# mcu.net
KiCad netlist of a schematic drawn in Altium Designer
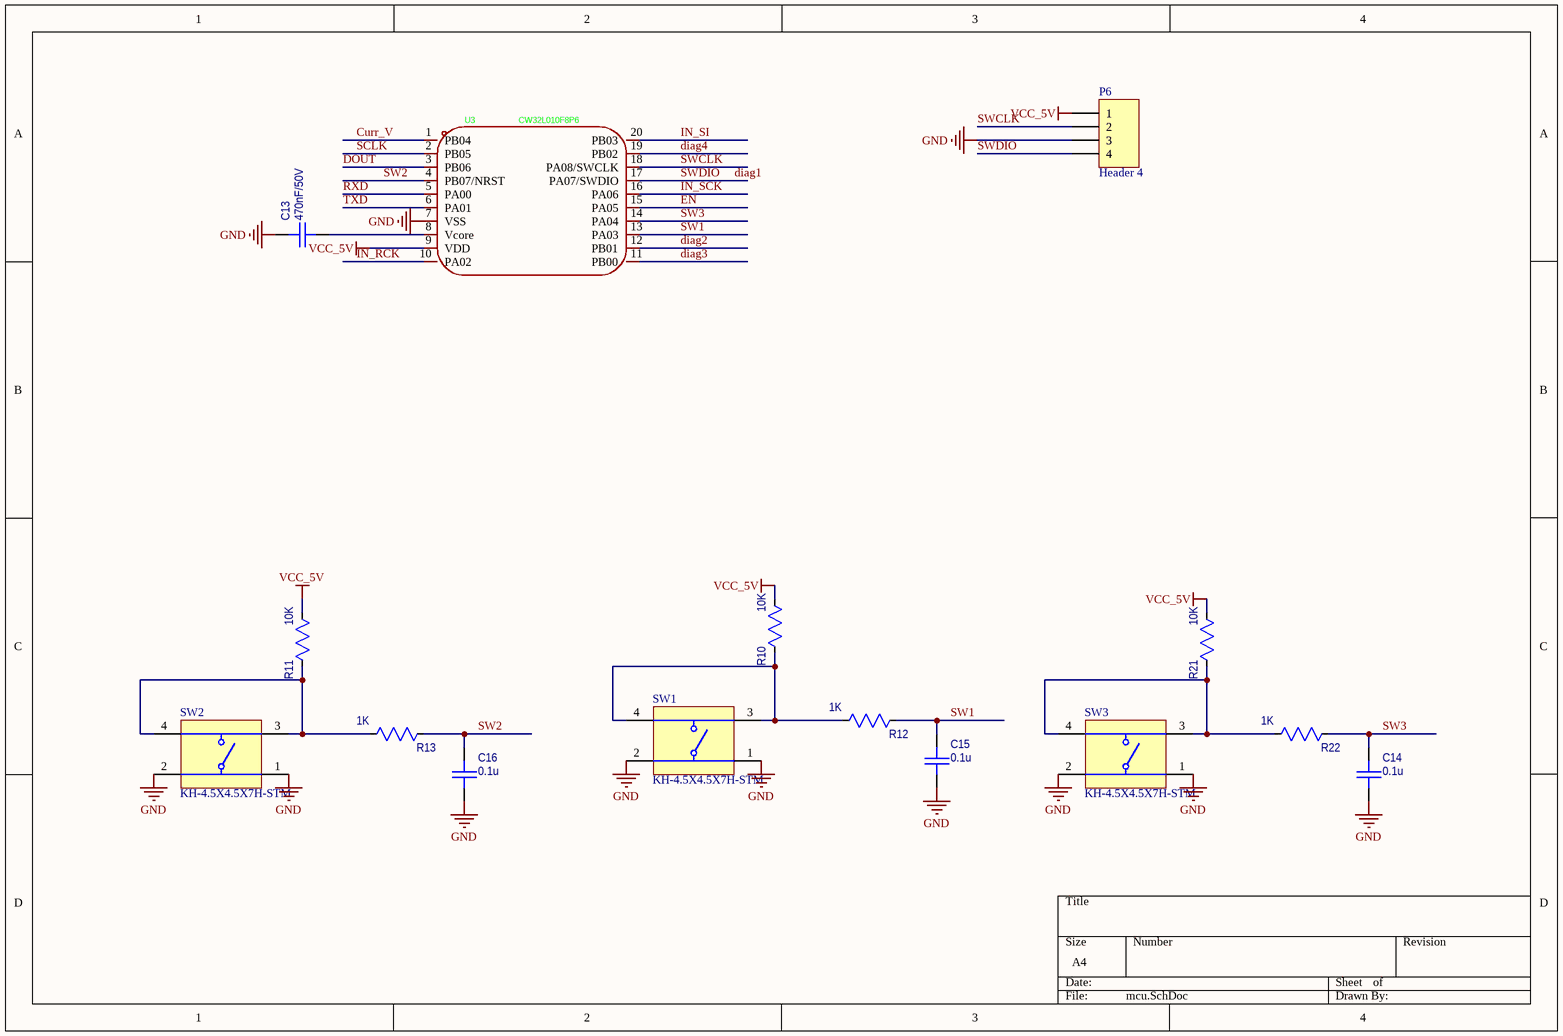
[diagram p0: mcu.SchDoc]

(export (version "E")
  (design (tool "Eeschema 10.0.6"))
  (components
    (comp (ref "C13")
      (value "470nF/50V")
      (footprint "CAPC1608X092N_0603")
      (description "Capacitor, MLCC")
      (fields (field (name "MANUFACTURER") "KEMET") (field (name "PARTNUMBER") "C0603C104M5RACTU"))
      (libsource (lib "Karl") (part "Capacitor_0603"))
    )
    (comp (ref "C14")
      (value "0.1u")
      (footprint "CAPC1608X092N_0603")
      (description "Capacitor, MLCC")
      (fields (field (name "MANUFACTURER") "KEMET") (field (name "PARTNUMBER") "C0603C104M5RACTU"))
      (libsource (lib "Karl") (part "Capacitor_0603"))
    )
    (comp (ref "C15")
      (value "0.1u")
      (footprint "CAPC1608X092N_0603")
      (description "Capacitor, MLCC")
      (fields (field (name "MANUFACTURER") "KEMET") (field (name "PARTNUMBER") "C0603C104M5RACTU"))
      (libsource (lib "Karl") (part "Capacitor_0603"))
    )
    (comp (ref "C16")
      (value "0.1u")
      (footprint "CAPC1608X092N_0603")
      (description "Capacitor, MLCC")
      (fields (field (name "MANUFACTURER") "KEMET") (field (name "PARTNUMBER") "C0603C104M5RACTU"))
      (libsource (lib "Karl") (part "Capacitor_0603"))
    )
    (comp (ref "P6")
      (value "Header 4")
      (footprint "1.27-4P")
      (fields (field (name "PUBLISHER") "Altium Limited"))
      (libsource (lib "Miscellaneous Connectors") (part "Header 4"))
    )
    (comp (ref "R10")
      (value "10K")
      (footprint "RESC1608X055N_0603")
      (description "Resistor, Standard")
      (fields (field (name "MANUFACTURER") "Yageo") (field (name "PARTNUMBER") "RC0603FR-1075KL"))
      (libsource (lib "Karl") (part "Resistor_0603"))
    )
    (comp (ref "R11")
      (value "10K")
      (footprint "RESC1608X055N_0603")
      (description "Resistor, Standard")
      (fields (field (name "MANUFACTURER") "Yageo") (field (name "PARTNUMBER") "RC0603FR-1075KL"))
      (libsource (lib "Karl") (part "Resistor_0603"))
    )
    (comp (ref "R12")
      (value "1K")
      (footprint "RESC1608X055N_0603")
      (description "Resistor, Standard")
      (fields (field (name "MANUFACTURER") "Yageo") (field (name "PARTNUMBER") "RC0603FR-1075KL"))
      (libsource (lib "Karl") (part "Resistor_0603"))
    )
    (comp (ref "R13")
      (value "1K")
      (footprint "RESC1608X055N_0603")
      (description "Resistor, Standard")
      (fields (field (name "MANUFACTURER") "Yageo") (field (name "PARTNUMBER") "RC0603FR-1075KL"))
      (libsource (lib "Karl") (part "Resistor_0603"))
    )
    (comp (ref "R21")
      (value "10K")
      (footprint "RESC1608X055N_0603")
      (description "Resistor, Standard")
      (fields (field (name "MANUFACTURER") "Yageo") (field (name "PARTNUMBER") "RC0603FR-1075KL"))
      (libsource (lib "Karl") (part "Resistor_0603"))
    )
    (comp (ref "R22")
      (value "1K")
      (footprint "RESC1608X055N_0603")
      (description "Resistor, Standard")
      (fields (field (name "MANUFACTURER") "Yageo") (field (name "PARTNUMBER") "RC0603FR-1075KL"))
      (libsource (lib "Karl") (part "Resistor_0603"))
    )
    (comp (ref "SW1")
      (value "KH-4.5X4.5X7H-STM")
      (footprint "SW-SMD_4P-L4.5-W4.5-P3.00-LS6.8:SW-SMD_4P-L4.5-W4.5-P3.00-LS6.8")
      (description "Tactile Switch, 6 × 6 mm, Height 5.0mm, 4-Pin THD")
      (fields (field (name "PARTNUMBER") "J1L0503110"))
      (libsource (lib "Bogen") (part "J1L0503110"))
    )
    (comp (ref "SW2")
      (value "KH-4.5X4.5X7H-STM")
      (footprint "SW-SMD_4P-L4.5-W4.5-P3.00-LS6.8:SW-SMD_4P-L4.5-W4.5-P3.00-LS6.8")
      (description "Tactile Switch, 6 × 6 mm, Height 5.0mm, 4-Pin THD")
      (fields (field (name "PARTNUMBER") "J1L0503110"))
      (libsource (lib "Bogen") (part "J1L0503110"))
    )
    (comp (ref "SW3")
      (value "KH-4.5X4.5X7H-STM")
      (footprint "SW-SMD_4P-L4.5-W4.5-P3.00-LS6.8:SW-SMD_4P-L4.5-W4.5-P3.00-LS6.8")
      (description "Tactile Switch, 6 × 6 mm, Height 5.0mm, 4-Pin THD")
      (fields (field (name "PARTNUMBER") "J1L0503110"))
      (libsource (lib "Bogen") (part "J1L0503110"))
    )
    (comp (ref "U3")
      (value "CW32L010F8P6")
      (footprint "TSSOP-20_L6.5-W4.4-P0.65-LS6.4-BL:TSSOP-20_L6.5-W4.4-P0.65-LS6.4-BL")
      (fields (field (name "MANUFACTURER") "CW(芯源)"))
      (libsource (lib "altium-import") (part "root_0_CW32L010F8P6_"))
    )
  )
  (nets
    (net (code "1") (name "/Curr_V") (class "Default")
      (node (ref "U3") (pin "1") (pinfunction "PB04_1") (pintype "passive"))
    )
    (net (code "2") (name "/DOUT") (class "Default")
      (node (ref "U3") (pin "3") (pinfunction "PB06_3") (pintype "passive"))
    )
    (net (code "3") (name "/EN") (class "Default")
      (node (ref "U3") (pin "15") (pinfunction "PA05_15") (pintype "passive"))
    )
    (net (code "4") (name "/IN_RCK") (class "Default")
      (node (ref "U3") (pin "10") (pinfunction "PA02_10") (pintype "passive"))
    )
    (net (code "5") (name "/IN_SCK") (class "Default")
      (node (ref "U3") (pin "16") (pinfunction "PA06_16") (pintype "passive"))
    )
    (net (code "6") (name "/IN_SI") (class "Default")
      (node (ref "U3") (pin "20") (pinfunction "PB03_20") (pintype "passive"))
    )
    (net (code "7") (name "/RXD") (class "Default")
      (node (ref "U3") (pin "5") (pinfunction "PA00_5") (pintype "passive"))
    )
    (net (code "8") (name "/SCLK") (class "Default")
      (node (ref "U3") (pin "2") (pinfunction "PB05_2") (pintype "passive"))
    )
    (net (code "9") (name "/SW1") (class "Default")
      (node (ref "C15") (pin "1") (pinfunction "1_1") (pintype "passive"))
      (node (ref "R12") (pin "2") (pinfunction "2_2") (pintype "passive"))
      (node (ref "U3") (pin "13") (pinfunction "PA03_13") (pintype "passive"))
    )
    (net (code "10") (name "/SW2") (class "Default")
      (node (ref "C16") (pin "1") (pinfunction "1_1") (pintype "passive"))
      (node (ref "R13") (pin "2") (pinfunction "2_2") (pintype "passive"))
      (node (ref "U3") (pin "4") (pinfunction "PB07/NRST_4") (pintype "passive"))
    )
    (net (code "11") (name "/SW3") (class "Default")
      (node (ref "C14") (pin "1") (pinfunction "1_1") (pintype "passive"))
      (node (ref "R22") (pin "2") (pinfunction "2_2") (pintype "passive"))
      (node (ref "U3") (pin "14") (pinfunction "PA04_14") (pintype "passive"))
    )
    (net (code "12") (name "/SWCLK") (class "Default")
      (node (ref "P6") (pin "2") (pinfunction "2_2") (pintype "passive"))
      (node (ref "U3") (pin "18") (pinfunction "PA08/SWCLK_18") (pintype "passive"))
    )
    (net (code "13") (name "/SWDIO") (class "Default")
      (node (ref "P6") (pin "4") (pinfunction "4_4") (pintype "passive"))
      (node (ref "U3") (pin "17") (pinfunction "PA07/SWDIO_17") (pintype "passive"))
    )
    (net (code "14") (name "/TXD") (class "Default")
      (node (ref "U3") (pin "6") (pinfunction "PA01_6") (pintype "passive"))
    )
    (net (code "15") (name "/diag2") (class "Default")
      (node (ref "U3") (pin "12") (pinfunction "PB01_12") (pintype "passive"))
    )
    (net (code "16") (name "/diag3") (class "Default")
      (node (ref "U3") (pin "11") (pinfunction "PB00_11") (pintype "passive"))
    )
    (net (code "17") (name "/diag4") (class "Default")
      (node (ref "U3") (pin "19") (pinfunction "PB02_19") (pintype "passive"))
    )
    (net (code "18") (name "GND") (class "Default")
      (node (ref "C13") (pin "1") (pinfunction "1_1") (pintype "passive"))
      (node (ref "C14") (pin "2") (pinfunction "2_2") (pintype "passive"))
      (node (ref "C15") (pin "2") (pinfunction "2_2") (pintype "passive"))
      (node (ref "C16") (pin "2") (pinfunction "2_2") (pintype "passive"))
      (node (ref "P6") (pin "3") (pinfunction "3_3") (pintype "passive"))
      (node (ref "SW1") (pin "1") (pinfunction "1_1") (pintype "passive"))
      (node (ref "SW1") (pin "2") (pinfunction "2_2") (pintype "passive"))
      (node (ref "SW2") (pin "1") (pinfunction "1_1") (pintype "passive"))
      (node (ref "SW2") (pin "2") (pinfunction "2_2") (pintype "passive"))
      (node (ref "SW3") (pin "1") (pinfunction "1_1") (pintype "passive"))
      (node (ref "SW3") (pin "2") (pinfunction "2_2") (pintype "passive"))
      (node (ref "U3") (pin "7") (pinfunction "VSS_7") (pintype "passive"))
    )
    (net (code "19") (name "Net-(R10-Pad2)") (class "Default")
      (node (ref "R10") (pin "2") (pinfunction "2_2") (pintype "passive"))
      (node (ref "R12") (pin "1") (pinfunction "1_1") (pintype "passive"))
      (node (ref "SW1") (pin "3") (pinfunction "3_3") (pintype "passive"))
      (node (ref "SW1") (pin "4") (pinfunction "4_4") (pintype "passive"))
    )
    (net (code "20") (name "Net-(R11-Pad2)") (class "Default")
      (node (ref "R11") (pin "2") (pinfunction "2_2") (pintype "passive"))
      (node (ref "R13") (pin "1") (pinfunction "1_1") (pintype "passive"))
      (node (ref "SW2") (pin "3") (pinfunction "3_3") (pintype "passive"))
      (node (ref "SW2") (pin "4") (pinfunction "4_4") (pintype "passive"))
    )
    (net (code "21") (name "Net-(R21-Pad2)") (class "Default")
      (node (ref "R21") (pin "2") (pinfunction "2_2") (pintype "passive"))
      (node (ref "R22") (pin "1") (pinfunction "1_1") (pintype "passive"))
      (node (ref "SW3") (pin "3") (pinfunction "3_3") (pintype "passive"))
      (node (ref "SW3") (pin "4") (pinfunction "4_4") (pintype "passive"))
    )
    (net (code "22") (name "Net-(U3-Vcore)") (class "Default")
      (node (ref "C13") (pin "2") (pinfunction "2_2") (pintype "passive"))
      (node (ref "U3") (pin "8") (pinfunction "Vcore_8") (pintype "passive"))
    )
    (net (code "23") (name "VCC_5V") (class "Default")
      (node (ref "P6") (pin "1") (pinfunction "1_1") (pintype "passive"))
      (node (ref "R10") (pin "1") (pinfunction "1_1") (pintype "passive"))
      (node (ref "R11") (pin "1") (pinfunction "1_1") (pintype "passive"))
      (node (ref "R21") (pin "1") (pinfunction "1_1") (pintype "passive"))
      (node (ref "U3") (pin "9") (pinfunction "VDD_9") (pintype "passive"))
    )
  )
)
